# Pressure_Sensor.net
KiCad netlist of a schematic drawn in Altium Designer
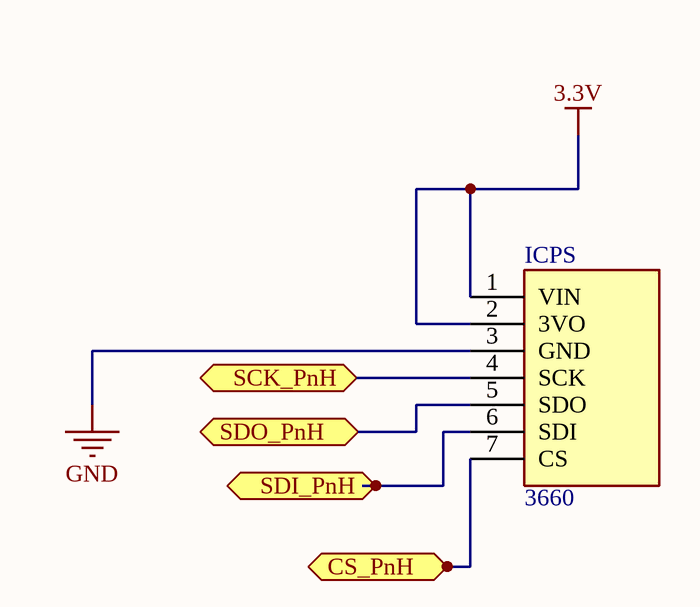
[diagram p0: Pressure Sensor.SchDoc]

(export (version "E")
  (design (tool "Eeschema 10.0.6"))
  (components
    (comp (ref "ICPS")
      (value "3660")
      (footprint "SamacSys:3660")
      (description "Integrated Circuit")
      (fields (field (name "MOUSER PART NUMBER") "485-3660"))
      (libsource (lib "*") (part "3660"))
    )
  )
  (nets
    (net (code "1") (name "/CS_PnH") (class "Default")
      (node (ref "ICPS") (pin "7") (pinfunction "CS_7") (pintype "passive"))
    )
    (net (code "2") (name "/SCK_PnH") (class "Default")
      (node (ref "ICPS") (pin "4") (pinfunction "SCK_4") (pintype "passive"))
    )
    (net (code "3") (name "/SDI_PnH") (class "Default")
      (node (ref "ICPS") (pin "6") (pinfunction "SDI_6") (pintype "passive"))
    )
    (net (code "4") (name "/SDO_PnH") (class "Default")
      (node (ref "ICPS") (pin "5") (pinfunction "SDO_5") (pintype "passive"))
    )
    (net (code "5") (name "3.3V") (class "Default")
      (node (ref "ICPS") (pin "1") (pinfunction "VIN_1") (pintype "passive"))
      (node (ref "ICPS") (pin "2") (pinfunction "3VO_2") (pintype "passive"))
    )
    (net (code "6") (name "GND") (class "Default")
      (node (ref "ICPS") (pin "3") (pinfunction "GND_3") (pintype "passive"))
    )
  )
)
